# STM32F7.net
KiCad netlist of a schematic drawn in Altium Designer
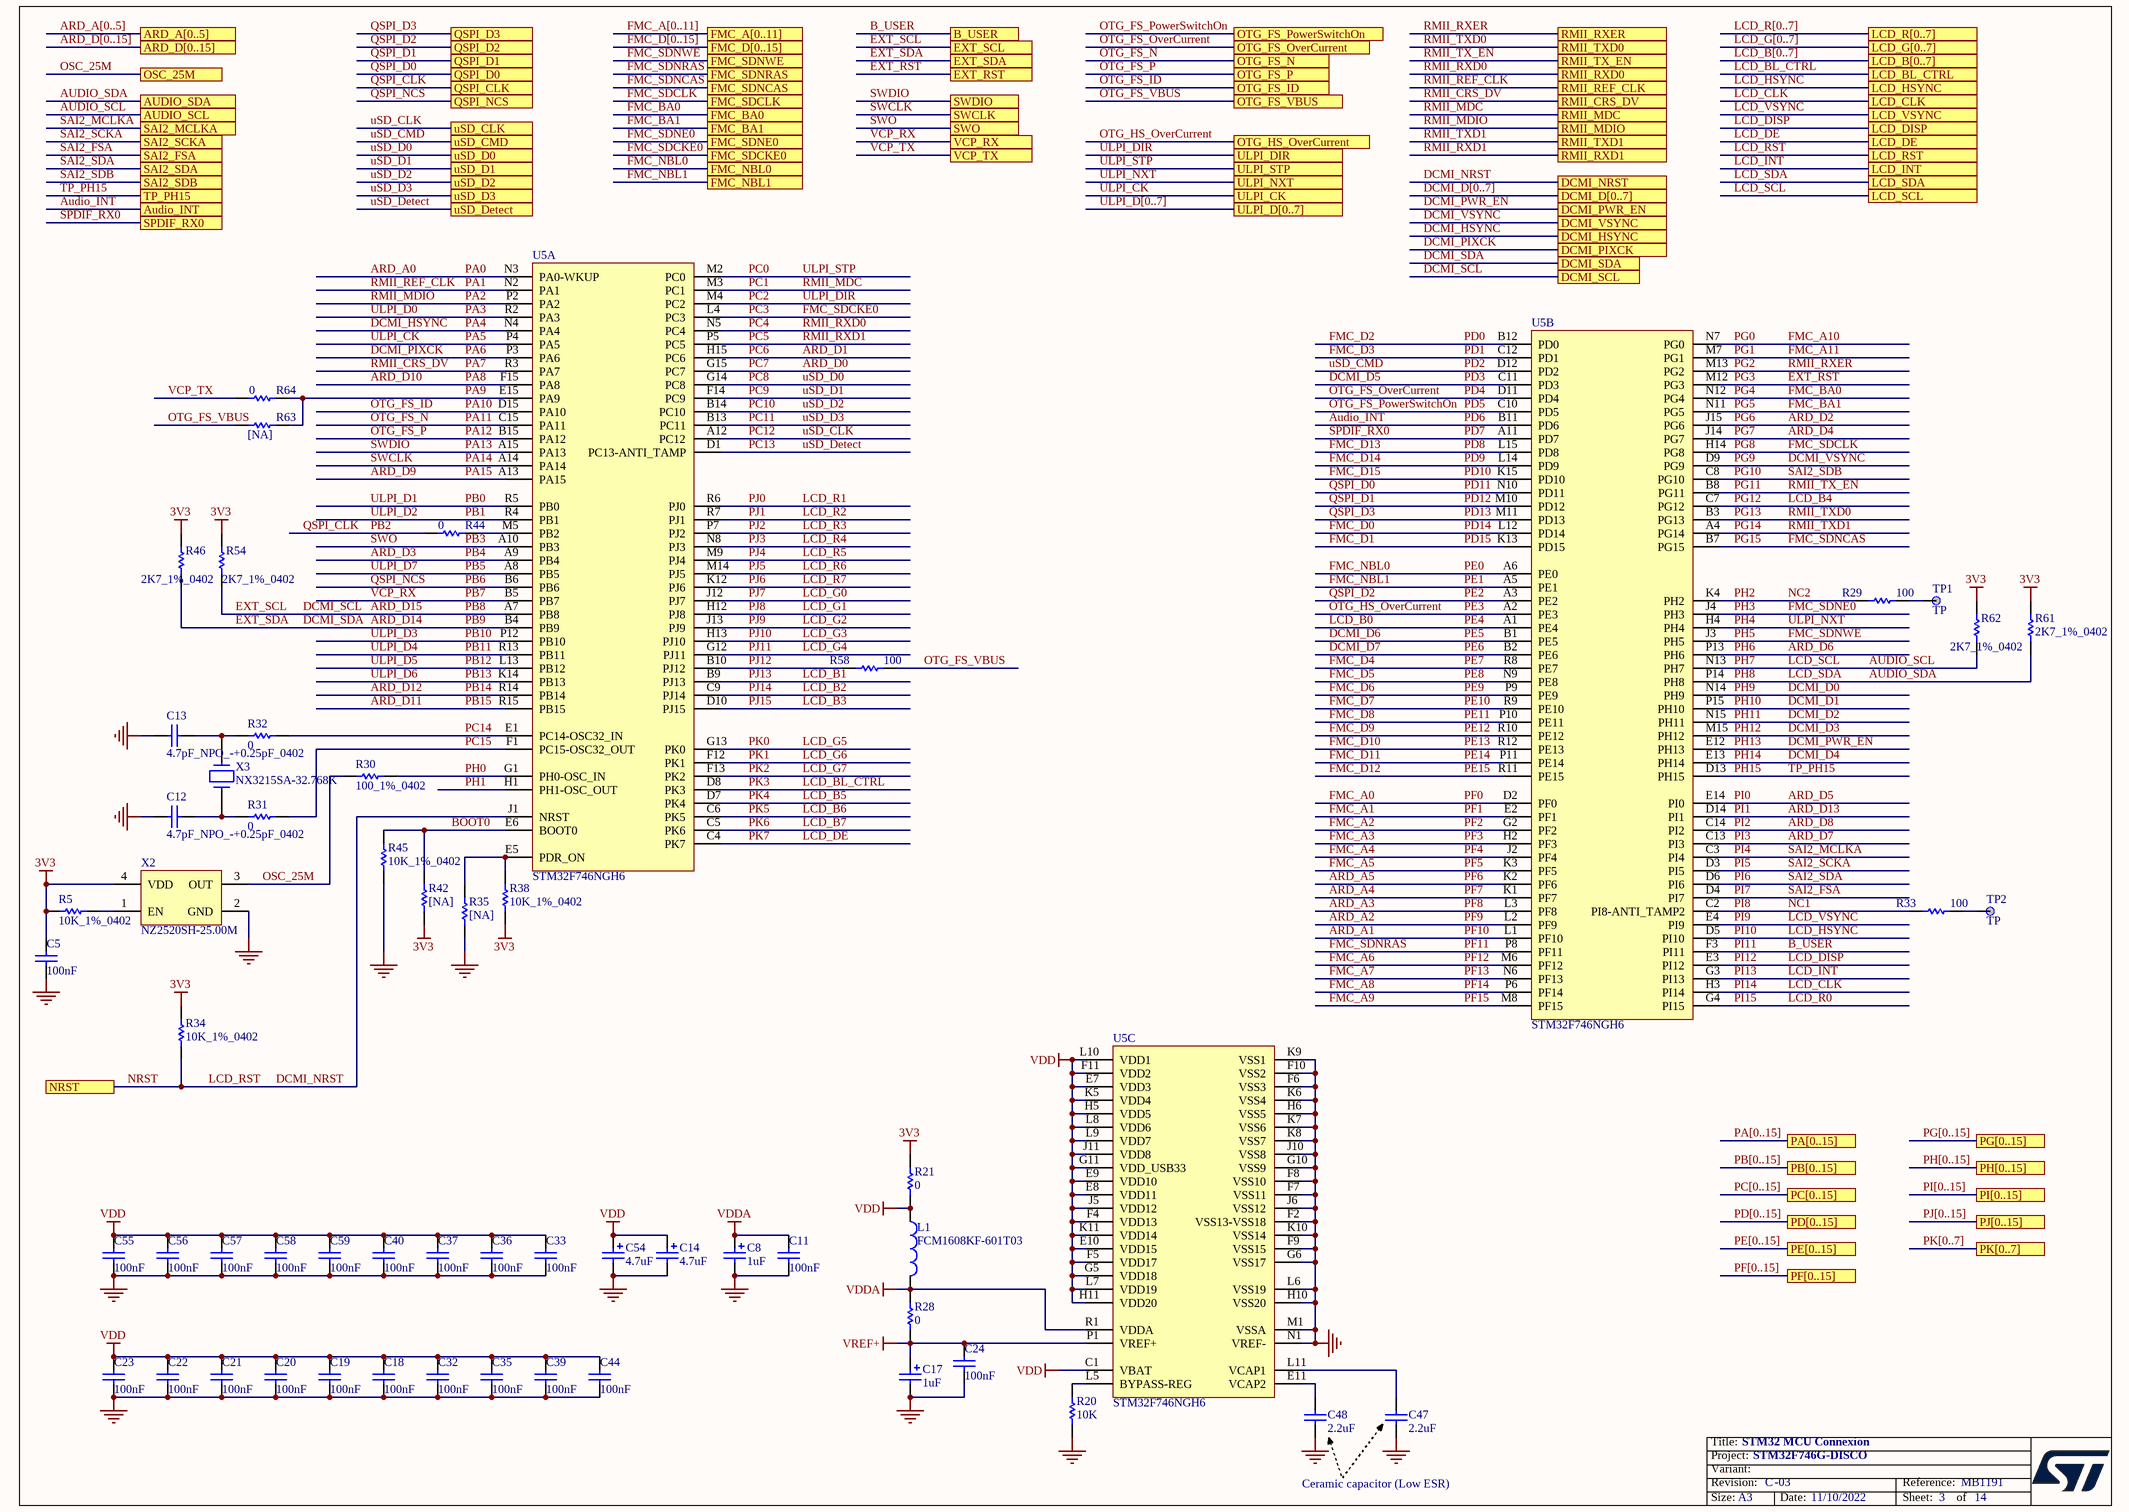
[diagram p0: STM32F7.SchDoc]

(export (version "E")
  (design (tool "Eeschema 10.0.6"))
  (components
    (comp (ref "C5")
      (value "100nF")
      (footprint "0402C")
      (description "Capacitor,100nF,16V,X7R,10%,0402,YAGEO")
      (libsource (lib "MCD_TOOLS") (part "Cap_100nF_X7R_10%_0402"))
    )
    (comp (ref "C8")
      (value "1uF")
      (footprint "TAN-A")
      (description "Polarized Capacitor,1uF,16V,10%,typeA,AVX")
      (libsource (lib "MCD_TOOLS") (part "Cap_1uF_POL_10%_TANA"))
    )
    (comp (ref "C11")
      (value "100nF")
      (footprint "0402C")
      (description "Capacitor,100nF,16V,X7R,10%,0402,YAGEO")
      (libsource (lib "MCD_TOOLS") (part "Cap_100nF_X7R_10%_0402"))
    )
    (comp (ref "C12")
      (value "4.7pF_NPO_-+0.25pF_0402")
      (footprint "0402C")
      (description "Capacitor, 4.7pF, 50V, NPO, -+0.25pF, 0402, YAGEO")
      (libsource (lib "MCD_TOOLS") (part "Cap_4.7pF_NPO_-+0.25pF_0402"))
    )
    (comp (ref "C13")
      (value "4.7pF_NPO_-+0.25pF_0402")
      (footprint "0402C")
      (description "Capacitor, 4.7pF, 50V, NPO, -+0.25pF, 0402, YAGEO")
      (libsource (lib "MCD_TOOLS") (part "Cap_4.7pF_NPO_-+0.25pF_0402"))
    )
    (comp (ref "C14")
      (value "4.7uF")
      (footprint "TAN-A")
      (description "Polarized Capacitor,4.7uF,16V,10%,typeA,AVX")
      (libsource (lib "MCD_TOOLS") (part "Cap_4.7uF_POL_10%_TANA"))
    )
    (comp (ref "C17")
      (value "1uF")
      (footprint "TAN-A")
      (description "Polarized Capacitor,1uF,16V,10%,typeA,AVX")
      (libsource (lib "MCD_TOOLS") (part "Cap_1uF_POL_10%_TANA"))
    )
    (comp (ref "C18")
      (value "100nF")
      (footprint "0402C")
      (description "Capacitor,100nF,16V,X7R,10%,0402,YAGEO")
      (libsource (lib "MCD_TOOLS") (part "Cap_100nF_X7R_10%_0402"))
    )
    (comp (ref "C19")
      (value "100nF")
      (footprint "0402C")
      (description "Capacitor,100nF,16V,X7R,10%,0402,YAGEO")
      (libsource (lib "MCD_TOOLS") (part "Cap_100nF_X7R_10%_0402"))
    )
    (comp (ref "C20")
      (value "100nF")
      (footprint "0402C")
      (description "Capacitor,100nF,16V,X7R,10%,0402,YAGEO")
      (libsource (lib "MCD_TOOLS") (part "Cap_100nF_X7R_10%_0402"))
    )
    (comp (ref "C21")
      (value "100nF")
      (footprint "0402C")
      (description "Capacitor,100nF,16V,X7R,10%,0402,YAGEO")
      (libsource (lib "MCD_TOOLS") (part "Cap_100nF_X7R_10%_0402"))
    )
    (comp (ref "C22")
      (value "100nF")
      (footprint "0402C")
      (description "Capacitor,100nF,16V,X7R,10%,0402,YAGEO")
      (libsource (lib "MCD_TOOLS") (part "Cap_100nF_X7R_10%_0402"))
    )
    (comp (ref "C23")
      (value "100nF")
      (footprint "0402C")
      (description "Capacitor,100nF,16V,X7R,10%,0402,YAGEO")
      (libsource (lib "MCD_TOOLS") (part "Cap_100nF_X7R_10%_0402"))
    )
    (comp (ref "C24")
      (value "100nF")
      (footprint "0402C")
      (description "Capacitor,100nF,16V,X7R,10%,0402,YAGEO")
      (libsource (lib "MCD_TOOLS") (part "Cap_100nF_X7R_10%_0402"))
    )
    (comp (ref "C32")
      (value "100nF")
      (footprint "0402C")
      (description "Capacitor,100nF,16V,X7R,10%,0402,YAGEO")
      (libsource (lib "MCD_TOOLS") (part "Cap_100nF_X7R_10%_0402"))
    )
    (comp (ref "C33")
      (value "100nF")
      (footprint "0402C")
      (description "Capacitor,100nF,16V,X7R,10%,0402,YAGEO")
      (libsource (lib "MCD_TOOLS") (part "Cap_100nF_X7R_10%_0402"))
    )
    (comp (ref "C35")
      (value "100nF")
      (footprint "0402C")
      (description "Capacitor,100nF,16V,X7R,10%,0402,YAGEO")
      (libsource (lib "MCD_TOOLS") (part "Cap_100nF_X7R_10%_0402"))
    )
    (comp (ref "C36")
      (value "100nF")
      (footprint "0402C")
      (description "Capacitor,100nF,16V,X7R,10%,0402,YAGEO")
      (libsource (lib "MCD_TOOLS") (part "Cap_100nF_X7R_10%_0402"))
    )
    (comp (ref "C37")
      (value "100nF")
      (footprint "0402C")
      (description "Capacitor,100nF,16V,X7R,10%,0402,YAGEO")
      (libsource (lib "MCD_TOOLS") (part "Cap_100nF_X7R_10%_0402"))
    )
    (comp (ref "C39")
      (value "100nF")
      (footprint "0402C")
      (description "Capacitor,100nF,16V,X7R,10%,0402,YAGEO")
      (libsource (lib "MCD_TOOLS") (part "Cap_100nF_X7R_10%_0402"))
    )
    (comp (ref "C40")
      (value "100nF")
      (footprint "0402C")
      (description "Capacitor,100nF,16V,X7R,10%,0402,YAGEO")
      (libsource (lib "MCD_TOOLS") (part "Cap_100nF_X7R_10%_0402"))
    )
    (comp (ref "C44")
      (value "100nF")
      (footprint "0402C")
      (description "Capacitor,100nF,16V,X7R,10%,0402,YAGEO")
      (libsource (lib "MCD_TOOLS") (part "Cap_100nF_X7R_10%_0402"))
    )
    (comp (ref "C47")
      (value "2.2uF")
      (footprint "1206C")
      (description "Capacitor,2.2uF,16V, X7R,10%,1206,YAGEO")
      (libsource (lib "MCD_TOOLS") (part "Cap_2.2uF_X7R_10%_1206"))
    )
    (comp (ref "C48")
      (value "2.2uF")
      (footprint "1206C")
      (description "Capacitor,2.2uF,16V, X7R,10%,1206,YAGEO")
      (libsource (lib "MCD_TOOLS") (part "Cap_2.2uF_X7R_10%_1206"))
    )
    (comp (ref "C54")
      (value "4.7uF")
      (footprint "TAN-A")
      (description "Polarized Capacitor,4.7uF,16V,10%,typeA,AVX")
      (libsource (lib "MCD_TOOLS") (part "Cap_4.7uF_POL_10%_TANA"))
    )
    (comp (ref "C55")
      (value "100nF")
      (footprint "0402C")
      (description "Capacitor,100nF,16V,X7R,10%,0402,YAGEO")
      (libsource (lib "MCD_TOOLS") (part "Cap_100nF_X7R_10%_0402"))
    )
    (comp (ref "C56")
      (value "100nF")
      (footprint "0402C")
      (description "Capacitor,100nF,16V,X7R,10%,0402,YAGEO")
      (libsource (lib "MCD_TOOLS") (part "Cap_100nF_X7R_10%_0402"))
    )
    (comp (ref "C57")
      (value "100nF")
      (footprint "0402C")
      (description "Capacitor,100nF,16V,X7R,10%,0402,YAGEO")
      (libsource (lib "MCD_TOOLS") (part "Cap_100nF_X7R_10%_0402"))
    )
    (comp (ref "C58")
      (value "100nF")
      (footprint "0402C")
      (description "Capacitor,100nF,16V,X7R,10%,0402,YAGEO")
      (libsource (lib "MCD_TOOLS") (part "Cap_100nF_X7R_10%_0402"))
    )
    (comp (ref "C59")
      (value "100nF")
      (footprint "0402C")
      (description "Capacitor,100nF,16V,X7R,10%,0402,YAGEO")
      (libsource (lib "MCD_TOOLS") (part "Cap_100nF_X7R_10%_0402"))
    )
    (comp (ref "L1")
      (value "FCM1608KF-601T03")
      (footprint "0603L")
      (description "Bead,600R,350mA,0603,FCM1608KF-601T03,Tai-tech")
      (libsource (lib "MCD_TOOLS") (part "BEAD_600R_350MA_0603"))
    )
    (comp (ref "R5")
      (value "10K_1%_0402")
      (footprint "0402R")
      (description "Resistor,10K,0402,1%,YAGEO")
      (libsource (lib "MCD_TOOLS") (part "Res_10K_1%_0402"))
    )
    (comp (ref "R20")
      (value "10K")
      (footprint "0402R")
      (description "Resistor,10K,0402,1%,YAGEO")
      (libsource (lib "MCD_TOOLS") (part "Res_10K_1%_0402"))
    )
    (comp (ref "R21")
      (value "0")
      (footprint "0603R-GS")
      (description "Resistor,0,0603,5%,YAGEO")
      (libsource (lib "MCD_TOOLS") (part "Res_0_5%_0603"))
    )
    (comp (ref "R28")
      (value "0")
      (footprint "0603R-GS")
      (description "Resistor,0,0603,5%,YAGEO")
      (libsource (lib "MCD_TOOLS") (part "Res_0_5%_0603"))
    )
    (comp (ref "R29")
      (value "100")
      (footprint "0402R")
      (description "Resistor,100,0402,1%,YAGEO")
      (libsource (lib "MCD_TOOLS") (part "Res_100_1%_0402"))
    )
    (comp (ref "R30")
      (value "100_1%_0402")
      (footprint "0402R")
      (description "Resistor,100,0402,1%,YAGEO")
      (libsource (lib "MCD_TOOLS") (part "Res_100_1%_0402"))
    )
    (comp (ref "R31")
      (value "0")
      (footprint "0402R")
      (description "Resistor,0,0402,5%,YAGEO")
      (libsource (lib "MCD_TOOLS") (part "Res_0_5%_0402"))
    )
    (comp (ref "R32")
      (value "0")
      (footprint "0402R")
      (description "Resistor,0,0402,5%,YAGEO")
      (libsource (lib "MCD_TOOLS") (part "Res_0_5%_0402"))
    )
    (comp (ref "R33")
      (value "100")
      (footprint "0402R")
      (description "Resistor,100,0402,1%,YAGEO")
      (libsource (lib "MCD_TOOLS") (part "Res_100_1%_0402"))
    )
    (comp (ref "R34")
      (value "10K_1%_0402")
      (footprint "0402R")
      (description "Resistor,10K,0402,1%,YAGEO")
      (libsource (lib "MCD_TOOLS") (part "Res_10K_1%_0402"))
    )
    (comp (ref "R35")
      (value "[NA]")
      (footprint "0402R")
      (description "Resistor,[NA],0402")
      (libsource (lib "MCD_TOOLS") (part "Res_NA_0402"))
    )
    (comp (ref "R38")
      (value "10K_1%_0402")
      (footprint "0402R")
      (description "Resistor,10K,0402,1%,YAGEO")
      (libsource (lib "MCD_TOOLS") (part "Res_10K_1%_0402"))
    )
    (comp (ref "R42")
      (value "[NA]")
      (footprint "0402R")
      (description "Resistor,[NA],0402")
      (libsource (lib "MCD_TOOLS") (part "Res_NA_0402"))
    )
    (comp (ref "R44")
      (value "0")
      (footprint "0402R")
      (description "Resistor,0,0402,5%,YAGEO")
      (libsource (lib "MCD_TOOLS") (part "Res_0_5%_0402"))
    )
    (comp (ref "R45")
      (value "10K_1%_0402")
      (footprint "0402R")
      (description "Resistor,10K,0402,1%,YAGEO")
      (libsource (lib "MCD_TOOLS") (part "Res_10K_1%_0402"))
    )
    (comp (ref "R46")
      (value "2K7_1%_0402")
      (footprint "0402R")
      (description "Resistor,2K7,0402,1%,YAGEO")
      (libsource (lib "MCD_TOOLS") (part "Res_2K7_1%_0402"))
    )
    (comp (ref "R54")
      (value "2K7_1%_0402")
      (footprint "0402R")
      (description "Resistor,2K7,0402,1%,YAGEO")
      (libsource (lib "MCD_TOOLS") (part "Res_2K7_1%_0402"))
    )
    (comp (ref "R58")
      (value "100")
      (footprint "0402R")
      (description "Resistor,100,0402,1%,YAGEO")
      (libsource (lib "MCD_TOOLS") (part "Res_100_1%_0402"))
    )
    (comp (ref "R61")
      (value "2K7_1%_0402")
      (footprint "0402R")
      (description "Resistor,2K7,0402,1%,YAGEO")
      (libsource (lib "MCD_TOOLS") (part "Res_2K7_1%_0402"))
    )
    (comp (ref "R62")
      (value "2K7_1%_0402")
      (footprint "0402R")
      (description "Resistor,2K7,0402,1%,YAGEO")
      (libsource (lib "MCD_TOOLS") (part "Res_2K7_1%_0402"))
    )
    (comp (ref "R63")
      (value "[NA]")
      (footprint "0402R")
      (description "Resistor,[NA],0402")
      (libsource (lib "MCD_TOOLS") (part "Res_NA_0402"))
    )
    (comp (ref "R64")
      (value "0")
      (footprint "0402R")
      (description "Resistor,0,0402,5%,YAGEO")
      (libsource (lib "MCD_TOOLS") (part "Res_0_5%_0402"))
    )
    (comp (ref "TP1")
      (value "TP")
      (footprint "SMDTEST-1MM")
      (description "Test Point")
      (libsource (lib "MCD_TOOLS") (part "TP"))
    )
    (comp (ref "TP2")
      (value "TP")
      (footprint "SMDTEST-1MM")
      (description "Test Point")
      (libsource (lib "MCD_TOOLS") (part "TP"))
    )
    (comp (ref "U5")
      (value "STM32F746NGH6")
      (footprint "BGA216_0R8_13X13_SKT")
      (description "STM32F746NGH6 (STM32F7 Birdie) TBGA216")
      (libsource (lib "MCD_TOOLS") (part "STM32F746NGH6U"))
    )
    (comp (ref "X2")
      (value "NZ2520SH-25.00M")
      (footprint "NZ2520SH_4P")
      (description "Oscillator 25.00Mhz, -+50PPM, 3.3V, Temp -55 to +125°C")
      (libsource (lib "MCD_TOOLS") (part "OSC_25M_NZ2520SB"))
    )
    (comp (ref "X3")
      (value "NX3215SA-32.768K")
      (footprint "XTAL_2SM_3R2X1R5")
      (description "Crystal 32.768kHz, 6pF, -+20PPM, R=50K, SMD")
      (libsource (lib "MCD_TOOLS") (part "XTAL_32K_NX3215SA"))
    )
  )
  (nets
    (net (code "1") (name "/ARD_A0") (class "Default")
      (node (ref "U5") (pin "N3") (pinfunction "PA0-WKUP_N3") (pintype "passive"))
    )
    (net (code "2") (name "/ARD_A1") (class "Default")
      (node (ref "U5") (pin "L1") (pinfunction "PF10_L1") (pintype "passive"))
    )
    (net (code "3") (name "/ARD_A2") (class "Default")
      (node (ref "U5") (pin "L2") (pinfunction "PF9_L2") (pintype "passive"))
    )
    (net (code "4") (name "/ARD_A3") (class "Default")
      (node (ref "U5") (pin "L3") (pinfunction "PF8_L3") (pintype "passive"))
    )
    (net (code "5") (name "/ARD_A4") (class "Default")
      (node (ref "U5") (pin "K1") (pinfunction "PF7_K1") (pintype "passive"))
    )
    (net (code "6") (name "/ARD_A5") (class "Default")
      (node (ref "U5") (pin "K2") (pinfunction "PF6_K2") (pintype "passive"))
    )
    (net (code "8") (name "/ARD_D0") (class "Default")
      (node (ref "U5") (pin "G15") (pinfunction "PC7_G15") (pintype "passive"))
    )
    (net (code "9") (name "/ARD_D1") (class "Default")
      (node (ref "U5") (pin "H15") (pinfunction "PC6_H15") (pintype "passive"))
    )
    (net (code "10") (name "/ARD_D2") (class "Default")
      (node (ref "U5") (pin "J15") (pinfunction "PG6_J15") (pintype "passive"))
    )
    (net (code "11") (name "/ARD_D3") (class "Default")
      (node (ref "U5") (pin "A9") (pinfunction "PB4_A9") (pintype "passive"))
    )
    (net (code "12") (name "/ARD_D4") (class "Default")
      (node (ref "U5") (pin "J14") (pinfunction "PG7_J14") (pintype "passive"))
    )
    (net (code "13") (name "/ARD_D5") (class "Default")
      (node (ref "U5") (pin "E14") (pinfunction "PI0_E14") (pintype "passive"))
    )
    (net (code "14") (name "/ARD_D6") (class "Default")
      (node (ref "U5") (pin "P13") (pinfunction "PH6_P13") (pintype "passive"))
    )
    (net (code "15") (name "/ARD_D7") (class "Default")
      (node (ref "U5") (pin "C13") (pinfunction "PI3_C13") (pintype "passive"))
    )
    (net (code "16") (name "/ARD_D8") (class "Default")
      (node (ref "U5") (pin "C14") (pinfunction "PI2_C14") (pintype "passive"))
    )
    (net (code "17") (name "/ARD_D9") (class "Default")
      (node (ref "U5") (pin "A13") (pinfunction "PA15_A13") (pintype "passive"))
    )
    (net (code "18") (name "/ARD_D10") (class "Default")
      (node (ref "U5") (pin "F15") (pinfunction "PA8_F15") (pintype "passive"))
    )
    (net (code "19") (name "/ARD_D11") (class "Default")
      (node (ref "U5") (pin "R15") (pinfunction "PB15_R15") (pintype "passive"))
    )
    (net (code "20") (name "/ARD_D12") (class "Default")
      (node (ref "U5") (pin "R14") (pinfunction "PB14_R14") (pintype "passive"))
    )
    (net (code "21") (name "/ARD_D13") (class "Default")
      (node (ref "U5") (pin "D14") (pinfunction "PI1_D14") (pintype "passive"))
    )
    (net (code "22") (name "/ARD_D14") (class "Default")
      (node (ref "R46") (pin "1") (pinfunction "1_1") (pintype "passive"))
      (node (ref "U5") (pin "B4") (pinfunction "PB9_B4") (pintype "passive"))
    )
    (net (code "23") (name "/ARD_D15") (class "Default")
      (node (ref "R54") (pin "1") (pinfunction "1_1") (pintype "passive"))
      (node (ref "U5") (pin "A7") (pinfunction "PB8_A7") (pintype "passive"))
    )
    (net (code "25") (name "/BOOT0") (class "Default")
      (node (ref "R42") (pin "2") (pinfunction "2_2") (pintype "passive"))
      (node (ref "R45") (pin "2") (pinfunction "2_2") (pintype "passive"))
      (node (ref "U5") (pin "E6") (pinfunction "BOOT0_E6") (pintype "passive"))
    )
    (net (code "26") (name "/DCMI_D0") (class "Default")
      (node (ref "U5") (pin "N14") (pinfunction "PH9_N14") (pintype "passive"))
    )
    (net (code "27") (name "/DCMI_D1") (class "Default")
      (node (ref "U5") (pin "P15") (pinfunction "PH10_P15") (pintype "passive"))
    )
    (net (code "28") (name "/DCMI_D2") (class "Default")
      (node (ref "U5") (pin "N15") (pinfunction "PH11_N15") (pintype "passive"))
    )
    (net (code "29") (name "/DCMI_D3") (class "Default")
      (node (ref "U5") (pin "M15") (pinfunction "PH12_M15") (pintype "passive"))
    )
    (net (code "30") (name "/DCMI_D4") (class "Default")
      (node (ref "U5") (pin "E13") (pinfunction "PH14_E13") (pintype "passive"))
    )
    (net (code "31") (name "/DCMI_D5") (class "Default")
      (node (ref "U5") (pin "C11") (pinfunction "PD3_C11") (pintype "passive"))
    )
    (net (code "32") (name "/DCMI_D6") (class "Default")
      (node (ref "U5") (pin "B1") (pinfunction "PE5_B1") (pintype "passive"))
    )
    (net (code "33") (name "/DCMI_D7") (class "Default")
      (node (ref "U5") (pin "B2") (pinfunction "PE6_B2") (pintype "passive"))
    )
    (net (code "35") (name "/DCMI_NRST") (class "Default")
      (node (ref "R34") (pin "1") (pinfunction "1_1") (pintype "passive"))
      (node (ref "U5") (pin "J1") (pinfunction "NRST_J1") (pintype "passive"))
    )
    (net (code "36") (name "/FMC_A0") (class "Default")
      (node (ref "U5") (pin "D2") (pinfunction "PF0_D2") (pintype "passive"))
    )
    (net (code "37") (name "/FMC_A1") (class "Default")
      (node (ref "U5") (pin "E2") (pinfunction "PF1_E2") (pintype "passive"))
    )
    (net (code "38") (name "/FMC_A2") (class "Default")
      (node (ref "U5") (pin "G2") (pinfunction "PF2_G2") (pintype "passive"))
    )
    (net (code "39") (name "/FMC_A3") (class "Default")
      (node (ref "U5") (pin "H2") (pinfunction "PF3_H2") (pintype "passive"))
    )
    (net (code "40") (name "/FMC_A4") (class "Default")
      (node (ref "U5") (pin "J2") (pinfunction "PF4_J2") (pintype "passive"))
    )
    (net (code "41") (name "/FMC_A5") (class "Default")
      (node (ref "U5") (pin "K3") (pinfunction "PF5_K3") (pintype "passive"))
    )
    (net (code "42") (name "/FMC_A6") (class "Default")
      (node (ref "U5") (pin "M6") (pinfunction "PF12_M6") (pintype "passive"))
    )
    (net (code "43") (name "/FMC_A7") (class "Default")
      (node (ref "U5") (pin "N6") (pinfunction "PF13_N6") (pintype "passive"))
    )
    (net (code "44") (name "/FMC_A8") (class "Default")
      (node (ref "U5") (pin "P6") (pinfunction "PF14_P6") (pintype "passive"))
    )
    (net (code "45") (name "/FMC_A9") (class "Default")
      (node (ref "U5") (pin "M8") (pinfunction "PF15_M8") (pintype "passive"))
    )
    (net (code "46") (name "/FMC_A10") (class "Default")
      (node (ref "U5") (pin "N7") (pinfunction "PG0_N7") (pintype "passive"))
    )
    (net (code "47") (name "/FMC_A11") (class "Default")
      (node (ref "U5") (pin "M7") (pinfunction "PG1_M7") (pintype "passive"))
    )
    (net (code "49") (name "/FMC_D0") (class "Default")
      (node (ref "U5") (pin "L12") (pinfunction "PD14_L12") (pintype "passive"))
    )
    (net (code "50") (name "/FMC_D1") (class "Default")
      (node (ref "U5") (pin "K13") (pinfunction "PD15_K13") (pintype "passive"))
    )
    (net (code "51") (name "/FMC_D2") (class "Default")
      (node (ref "U5") (pin "B12") (pinfunction "PD0_B12") (pintype "passive"))
    )
    (net (code "52") (name "/FMC_D3") (class "Default")
      (node (ref "U5") (pin "C12") (pinfunction "PD1_C12") (pintype "passive"))
    )
    (net (code "53") (name "/FMC_D4") (class "Default")
      (node (ref "U5") (pin "R8") (pinfunction "PE7_R8") (pintype "passive"))
    )
    (net (code "54") (name "/FMC_D5") (class "Default")
      (node (ref "U5") (pin "N9") (pinfunction "PE8_N9") (pintype "passive"))
    )
    (net (code "55") (name "/FMC_D6") (class "Default")
      (node (ref "U5") (pin "P9") (pinfunction "PE9_P9") (pintype "passive"))
    )
    (net (code "56") (name "/FMC_D7") (class "Default")
      (node (ref "U5") (pin "R9") (pinfunction "PE10_R9") (pintype "passive"))
    )
    (net (code "57") (name "/FMC_D8") (class "Default")
      (node (ref "U5") (pin "P10") (pinfunction "PE11_P10") (pintype "passive"))
    )
    (net (code "58") (name "/FMC_D9") (class "Default")
      (node (ref "U5") (pin "R10") (pinfunction "PE12_R10") (pintype "passive"))
    )
    (net (code "59") (name "/FMC_D10") (class "Default")
      (node (ref "U5") (pin "R12") (pinfunction "PE13_R12") (pintype "passive"))
    )
    (net (code "60") (name "/FMC_D11") (class "Default")
      (node (ref "U5") (pin "P11") (pinfunction "PE14_P11") (pintype "passive"))
    )
    (net (code "61") (name "/FMC_D12") (class "Default")
      (node (ref "U5") (pin "R11") (pinfunction "PE15_R11") (pintype "passive"))
    )
    (net (code "62") (name "/FMC_D13") (class "Default")
      (node (ref "U5") (pin "L15") (pinfunction "PD8_L15") (pintype "passive"))
    )
    (net (code "63") (name "/FMC_D14") (class "Default")
      (node (ref "U5") (pin "L14") (pinfunction "PD9_L14") (pintype "passive"))
    )
    (net (code "64") (name "/FMC_D15") (class "Default")
      (node (ref "U5") (pin "K15") (pinfunction "PD10_K15") (pintype "passive"))
    )
    (net (code "66") (name "/LCD_B0") (class "Default")
      (node (ref "U5") (pin "A1") (pinfunction "PE4_A1") (pintype "passive"))
    )
    (net (code "67") (name "/LCD_B1") (class "Default")
      (node (ref "U5") (pin "B9") (pinfunction "PJ13_B9") (pintype "passive"))
    )
    (net (code "68") (name "/LCD_B2") (class "Default")
      (node (ref "U5") (pin "C9") (pinfunction "PJ14_C9") (pintype "passive"))
    )
    (net (code "69") (name "/LCD_B3") (class "Default")
      (node (ref "U5") (pin "D10") (pinfunction "PJ15_D10") (pintype "passive"))
    )
    (net (code "70") (name "/LCD_B4") (class "Default")
      (node (ref "U5") (pin "C7") (pinfunction "PG12_C7") (pintype "passive"))
    )
    (net (code "71") (name "/LCD_B5") (class "Default")
      (node (ref "U5") (pin "D7") (pinfunction "PK4_D7") (pintype "passive"))
    )
    (net (code "72") (name "/LCD_B6") (class "Default")
      (node (ref "U5") (pin "C6") (pinfunction "PK5_C6") (pintype "passive"))
    )
    (net (code "73") (name "/LCD_B7") (class "Default")
      (node (ref "U5") (pin "C5") (pinfunction "PK6_C5") (pintype "passive"))
    )
    (net (code "75") (name "/LCD_G0") (class "Default")
      (node (ref "U5") (pin "J12") (pinfunction "PJ7_J12") (pintype "passive"))
    )
    (net (code "76") (name "/LCD_G1") (class "Default")
      (node (ref "U5") (pin "H12") (pinfunction "PJ8_H12") (pintype "passive"))
    )
    (net (code "77") (name "/LCD_G2") (class "Default")
      (node (ref "U5") (pin "J13") (pinfunction "PJ9_J13") (pintype "passive"))
    )
    (net (code "78") (name "/LCD_G3") (class "Default")
      (node (ref "U5") (pin "H13") (pinfunction "PJ10_H13") (pintype "passive"))
    )
    (net (code "79") (name "/LCD_G4") (class "Default")
      (node (ref "U5") (pin "G12") (pinfunction "PJ11_G12") (pintype "passive"))
    )
    (net (code "80") (name "/LCD_G5") (class "Default")
      (node (ref "U5") (pin "G13") (pinfunction "PK0_G13") (pintype "passive"))
    )
    (net (code "81") (name "/LCD_G6") (class "Default")
      (node (ref "U5") (pin "F12") (pinfunction "PK1_F12") (pintype "passive"))
    )
    (net (code "82") (name "/LCD_G7") (class "Default")
      (node (ref "U5") (pin "F13") (pinfunction "PK2_F13") (pintype "passive"))
    )
    (net (code "84") (name "/LCD_R0") (class "Default")
      (node (ref "U5") (pin "G4") (pinfunction "PI15_G4") (pintype "passive"))
    )
    (net (code "85") (name "/LCD_R1") (class "Default")
      (node (ref "U5") (pin "R6") (pinfunction "PJ0_R6") (pintype "passive"))
    )
    (net (code "86") (name "/LCD_R2") (class "Default")
      (node (ref "U5") (pin "R7") (pinfunction "PJ1_R7") (pintype "passive"))
    )
    (net (code "87") (name "/LCD_R3") (class "Default")
      (node (ref "U5") (pin "P7") (pinfunction "PJ2_P7") (pintype "passive"))
    )
    (net (code "88") (name "/LCD_R4") (class "Default")
      (node (ref "U5") (pin "N8") (pinfunction "PJ3_N8") (pintype "passive"))
    )
    (net (code "89") (name "/LCD_R5") (class "Default")
      (node (ref "U5") (pin "M9") (pinfunction "PJ4_M9") (pintype "passive"))
    )
    (net (code "90") (name "/LCD_R6") (class "Default")
      (node (ref "U5") (pin "M14") (pinfunction "PJ5_M14") (pintype "passive"))
    )
    (net (code "91") (name "/LCD_R7") (class "Default")
      (node (ref "U5") (pin "K12") (pinfunction "PJ6_K12") (pintype "passive"))
    )
    (net (code "93") (name "/OSC_25M") (class "Default")
      (node (ref "R30") (pin "1") (pinfunction "1_1") (pintype "passive"))
      (node (ref "X2") (pin "3") (pinfunction "OUT_3") (pintype "passive"))
    )
    (net (code "94") (name "/OTG_FS_VBUS") (class "Default")
      (node (ref "R58") (pin "2") (pinfunction "2_2") (pintype "passive"))
      (node (ref "R63") (pin "1") (pinfunction "1_1") (pintype "passive"))
    )
    (net (code "95") (name "/PA1") (class "Default")
      (node (ref "U5") (pin "N2") (pinfunction "PA1_N2") (pintype "passive"))
    )
    (net (code "96") (name "/PA2") (class "Default")
      (node (ref "U5") (pin "P2") (pinfunction "PA2_P2") (pintype "passive"))
    )
    (net (code "97") (name "/PA4") (class "Default")
      (node (ref "U5") (pin "N4") (pinfunction "PA4_N4") (pintype "passive"))
    )
    (net (code "98") (name "/PA5") (class "Default")
      (node (ref "U5") (pin "P4") (pinfunction "PA5_P4") (pintype "passive"))
    )
    (net (code "99") (name "/PA6") (class "Default")
      (node (ref "U5") (pin "P3") (pinfunction "PA6_P3") (pintype "passive"))
    )
    (net (code "100") (name "/PA7") (class "Default")
      (node (ref "U5") (pin "R3") (pinfunction "PA7_R3") (pintype "passive"))
    )
    (net (code "101") (name "/PA9") (class "Default")
      (node (ref "R63") (pin "2") (pinfunction "2_2") (pintype "passive"))
      (node (ref "R64") (pin "2") (pinfunction "2_2") (pintype "passive"))
      (node (ref "U5") (pin "E15") (pinfunction "PA9_E15") (pintype "passive"))
    )
    (net (code "102") (name "/PA10") (class "Default")
      (node (ref "U5") (pin "D15") (pinfunction "PA10_D15") (pintype "passive"))
    )
    (net (code "103") (name "/PA11") (class "Default")
      (node (ref "U5") (pin "C15") (pinfunction "PA11_C15") (pintype "passive"))
    )
    (net (code "104") (name "/PA12") (class "Default")
      (node (ref "U5") (pin "B15") (pinfunction "PA12_B15") (pintype "passive"))
    )
    (net (code "105") (name "/PA13") (class "Default")
      (node (ref "U5") (pin "A15") (pinfunction "PA13_A15") (pintype "passive"))
    )
    (net (code "106") (name "/PA14") (class "Default")
      (node (ref "U5") (pin "A14") (pinfunction "PA14_A14") (pintype "passive"))
    )
    (net (code "108") (name "/PB2") (class "Default")
      (node (ref "R44") (pin "1") (pinfunction "1_1") (pintype "passive"))
    )
    (net (code "109") (name "/PB3") (class "Default")
      (node (ref "U5") (pin "A10") (pinfunction "PB3_A10") (pintype "passive"))
    )
    (net (code "110") (name "/PB6") (class "Default")
      (node (ref "U5") (pin "B6") (pinfunction "PB6_B6") (pintype "passive"))
    )
    (net (code "111") (name "/PB7") (class "Default")
      (node (ref "U5") (pin "B5") (pinfunction "PB7_B5") (pintype "passive"))
    )
    (net (code "113") (name "/PC0") (class "Default")
      (node (ref "U5") (pin "M2") (pinfunction "PC0_M2") (pintype "passive"))
    )
    (net (code "114") (name "/PC1") (class "Default")
      (node (ref "U5") (pin "M3") (pinfunction "PC1_M3") (pintype "passive"))
    )
    (net (code "115") (name "/PC2") (class "Default")
      (node (ref "U5") (pin "M4") (pinfunction "PC2_M4") (pintype "passive"))
    )
    (net (code "116") (name "/PC3") (class "Default")
      (node (ref "U5") (pin "L4") (pinfunction "PC3_L4") (pintype "passive"))
    )
    (net (code "117") (name "/PC4") (class "Default")
      (node (ref "U5") (pin "N5") (pinfunction "PC4_N5") (pintype "passive"))
    )
    (net (code "118") (name "/PC5") (class "Default")
      (node (ref "U5") (pin "P5") (pinfunction "PC5_P5") (pintype "passive"))
    )
    (net (code "119") (name "/PC8") (class "Default")
      (node (ref "U5") (pin "G14") (pinfunction "PC8_G14") (pintype "passive"))
    )
    (net (code "120") (name "/PC9") (class "Default")
      (node (ref "U5") (pin "F14") (pinfunction "PC9_F14") (pintype "passive"))
    )
    (net (code "121") (name "/PC10") (class "Default")
      (node (ref "U5") (pin "B14") (pinfunction "PC10_B14") (pintype "passive"))
    )
    (net (code "122") (name "/PC11") (class "Default")
      (node (ref "U5") (pin "B13") (pinfunction "PC11_B13") (pintype "passive"))
    )
    (net (code "123") (name "/PC12") (class "Default")
      (node (ref "U5") (pin "A12") (pinfunction "PC12_A12") (pintype "passive"))
    )
    (net (code "124") (name "/PC13") (class "Default")
      (node (ref "U5") (pin "D1") (pinfunction "PC13-ANTI_TAMP_D1") (pintype "passive"))
    )
    (net (code "125") (name "/PC14") (class "Default")
      (node (ref "R32") (pin "2") (pinfunction "2_2") (pintype "passive"))
      (node (ref "U5") (pin "E1") (pinfunction "PC14-OSC32_IN_E1") (pintype "passive"))
    )
    (net (code "126") (name "/PC15") (class "Default")
      (node (ref "R31") (pin "2") (pinfunction "2_2") (pintype "passive"))
      (node (ref "U5") (pin "F1") (pinfunction "PC15-OSC32_OUT_F1") (pintype "passive"))
    )
    (net (code "128") (name "/PD2") (class "Default")
      (node (ref "U5") (pin "D12") (pinfunction "PD2_D12") (pintype "passive"))
    )
    (net (code "129") (name "/PD4") (class "Default")
      (node (ref "U5") (pin "D11") (pinfunction "PD4_D11") (pintype "passive"))
    )
    (net (code "130") (name "/PD5") (class "Default")
      (node (ref "U5") (pin "C10") (pinfunction "PD5_C10") (pintype "passive"))
    )
    (net (code "131") (name "/PD6") (class "Default")
      (node (ref "U5") (pin "B11") (pinfunction "PD6_B11") (pintype "passive"))
    )
    (net (code "132") (name "/PD7") (class "Default")
      (node (ref "U5") (pin "A11") (pinfunction "PD7_A11") (pintype "passive"))
    )
    (net (code "133") (name "/PD11") (class "Default")
      (node (ref "U5") (pin "N10") (pinfunction "PD11_N10") (pintype "passive"))
    )
    (net (code "134") (name "/PD12") (class "Default")
      (node (ref "U5") (pin "M10") (pinfunction "PD12_M10") (pintype "passive"))
    )
    (net (code "135") (name "/PD13") (class "Default")
      (node (ref "U5") (pin "M11") (pinfunction "PD13_M11") (pintype "passive"))
    )
    (net (code "137") (name "/PE0") (class "Default")
      (node (ref "U5") (pin "A6") (pinfunction "PE0_A6") (pintype "passive"))
    )
    (net (code "138") (name "/PE1") (class "Default")
      (node (ref "U5") (pin "A5") (pinfunction "PE1_A5") (pintype "passive"))
    )
    (net (code "139") (name "/PE2") (class "Default")
      (node (ref "U5") (pin "A3") (pinfunction "PE2_A3") (pintype "passive"))
    )
    (net (code "140") (name "/PE3") (class "Default")
      (node (ref "U5") (pin "A2") (pinfunction "PE3_A2") (pintype "passive"))
    )
    (net (code "142") (name "/PF11") (class "Default")
      (node (ref "U5") (pin "P8") (pinfunction "PF11_P8") (pintype "passive"))
    )
    (net (code "144") (name "/PG2") (class "Default")
      (node (ref "U5") (pin "M13") (pinfunction "PG2_M13") (pintype "passive"))
    )
    (net (code "145") (name "/PG3") (class "Default")
      (node (ref "U5") (pin "M12") (pinfunction "PG3_M12") (pintype "passive"))
    )
    (net (code "146") (name "/PG4") (class "Default")
      (node (ref "U5") (pin "N12") (pinfunction "PG4_N12") (pintype "passive"))
    )
    (net (code "147") (name "/PG5") (class "Default")
      (node (ref "U5") (pin "N11") (pinfunction "PG5_N11") (pintype "passive"))
    )
    (net (code "148") (name "/PG8") (class "Default")
      (node (ref "U5") (pin "H14") (pinfunction "PG8_H14") (pintype "passive"))
    )
    (net (code "149") (name "/PG9") (class "Default")
      (node (ref "U5") (pin "D9") (pinfunction "PG9_D9") (pintype "passive"))
    )
    (net (code "150") (name "/PG10") (class "Default")
      (node (ref "U5") (pin "C8") (pinfunction "PG10_C8") (pintype "passive"))
    )
    (net (code "151") (name "/PG11") (class "Default")
      (node (ref "U5") (pin "B8") (pinfunction "PG11_B8") (pintype "passive"))
    )
    (net (code "152") (name "/PG13") (class "Default")
      (node (ref "U5") (pin "B3") (pinfunction "PG13_B3") (pintype "passive"))
    )
    (net (code "153") (name "/PG14") (class "Default")
      (node (ref "U5") (pin "A4") (pinfunction "PG14_A4") (pintype "passive"))
    )
    (net (code "154") (name "/PG15") (class "Default")
      (node (ref "U5") (pin "B7") (pinfunction "PG15_B7") (pintype "passive"))
    )
    (net (code "156") (name "/PH0") (class "Default")
      (node (ref "R30") (pin "2") (pinfunction "2_2") (pintype "passive"))
      (node (ref "U5") (pin "G1") (pinfunction "PH0-OSC_IN_G1") (pintype "passive"))
    )
    (net (code "157") (name "/PH1") (class "Default")
      (node (ref "U5") (pin "H1") (pinfunction "PH1-OSC_OUT_H1") (pintype "passive"))
    )
    (net (code "158") (name "/PH2") (class "Default")
      (node (ref "R29") (pin "1") (pinfunction "1_1") (pintype "passive"))
      (node (ref "U5") (pin "K4") (pinfunction "PH2_K4") (pintype "passive"))
    )
    (net (code "159") (name "/PH3") (class "Default")
      (node (ref "U5") (pin "J4") (pinfunction "PH3_J4") (pintype "passive"))
    )
    (net (code "160") (name "/PH4") (class "Default")
      (node (ref "U5") (pin "H4") (pinfunction "PH4_H4") (pintype "passive"))
    )
    (net (code "161") (name "/PH5") (class "Default")
      (node (ref "U5") (pin "J3") (pinfunction "PH5_J3") (pintype "passive"))
    )
    (net (code "162") (name "/PH7") (class "Default")
      (node (ref "R62") (pin "1") (pinfunction "1_1") (pintype "passive"))
      (node (ref "U5") (pin "N13") (pinfunction "PH7_N13") (pintype "passive"))
    )
    (net (code "163") (name "/PH8") (class "Default")
      (node (ref "R61") (pin "1") (pinfunction "1_1") (pintype "passive"))
      (node (ref "U5") (pin "P14") (pinfunction "PH8_P14") (pintype "passive"))
    )
    (net (code "164") (name "/PH13") (class "Default")
      (node (ref "U5") (pin "E12") (pinfunction "PH13_E12") (pintype "passive"))
    )
    (net (code "165") (name "/PH15") (class "Default")
      (node (ref "U5") (pin "D13") (pinfunction "PH15_D13") (pintype "passive"))
    )
    (net (code "167") (name "/PI4") (class "Default")
      (node (ref "U5") (pin "C3") (pinfunction "PI4_C3") (pintype "passive"))
    )
    (net (code "168") (name "/PI5") (class "Default")
      (node (ref "U5") (pin "D3") (pinfunction "PI5_D3") (pintype "passive"))
    )
    (net (code "169") (name "/PI6") (class "Default")
      (node (ref "U5") (pin "D6") (pinfunction "PI6_D6") (pintype "passive"))
    )
    (net (code "170") (name "/PI7") (class "Default")
      (node (ref "U5") (pin "D4") (pinfunction "PI7_D4") (pintype "passive"))
    )
    (net (code "171") (name "/PI8") (class "Default")
      (node (ref "R33") (pin "1") (pinfunction "1_1") (pintype "passive"))
      (node (ref "U5") (pin "C2") (pinfunction "PI8-ANTI_TAMP2_C2") (pintype "passive"))
    )
    (net (code "172") (name "/PI9") (class "Default")
      (node (ref "U5") (pin "E4") (pinfunction "PI9_E4") (pintype "passive"))
    )
    (net (code "173") (name "/PI10") (class "Default")
      (node (ref "U5") (pin "D5") (pinfunction "PI10_D5") (pintype "passive"))
    )
    (net (code "174") (name "/PI11") (class "Default")
      (node (ref "U5") (pin "F3") (pinfunction "PI11_F3") (pintype "passive"))
    )
    (net (code "175") (name "/PI12") (class "Default")
      (node (ref "U5") (pin "E3") (pinfunction "PI12_E3") (pintype "passive"))
    )
    (net (code "176") (name "/PI13") (class "Default")
      (node (ref "U5") (pin "G3") (pinfunction "PI13_G3") (pintype "passive"))
    )
    (net (code "177") (name "/PI14") (class "Default")
      (node (ref "U5") (pin "H3") (pinfunction "PI14_H3") (pintype "passive"))
    )
    (net (code "179") (name "/PJ12") (class "Default")
      (node (ref "R58") (pin "1") (pinfunction "1_1") (pintype "passive"))
      (node (ref "U5") (pin "B10") (pinfunction "PJ12_B10") (pintype "passive"))
    )
    (net (code "181") (name "/PK3") (class "Default")
      (node (ref "U5") (pin "D8") (pinfunction "PK3_D8") (pintype "passive"))
    )
    (net (code "182") (name "/PK7") (class "Default")
      (node (ref "U5") (pin "C4") (pinfunction "PK7_C4") (pintype "passive"))
    )
    (net (code "184") (name "/ULPI_D0") (class "Default")
      (node (ref "U5") (pin "R2") (pinfunction "PA3_R2") (pintype "passive"))
    )
    (net (code "185") (name "/ULPI_D1") (class "Default")
      (node (ref "U5") (pin "R5") (pinfunction "PB0_R5") (pintype "passive"))
    )
    (net (code "186") (name "/ULPI_D2") (class "Default")
      (node (ref "U5") (pin "R4") (pinfunction "PB1_R4") (pintype "passive"))
    )
    (net (code "187") (name "/ULPI_D3") (class "Default")
      (node (ref "U5") (pin "P12") (pinfunction "PB10_P12") (pintype "passive"))
    )
    (net (code "188") (name "/ULPI_D4") (class "Default")
      (node (ref "U5") (pin "R13") (pinfunction "PB11_R13") (pintype "passive"))
    )
    (net (code "189") (name "/ULPI_D5") (class "Default")
      (node (ref "U5") (pin "L13") (pinfunction "PB12_L13") (pintype "passive"))
    )
    (net (code "190") (name "/ULPI_D6") (class "Default")
      (node (ref "U5") (pin "K14") (pinfunction "PB13_K14") (pintype "passive"))
    )
    (net (code "191") (name "/ULPI_D7") (class "Default")
      (node (ref "U5") (pin "A8") (pinfunction "PB5_A8") (pintype "passive"))
    )
    (net (code "193") (name "/VCP_TX") (class "Default")
      (node (ref "R64") (pin "1") (pinfunction "1_1") (pintype "passive"))
    )
    (net (code "194") (name "3V3") (class "Default")
      (node (ref "C5") (pin "2") (pinfunction "2_2") (pintype "passive"))
      (node (ref "R21") (pin "2") (pinfunction "2_2") (pintype "passive"))
      (node (ref "R34") (pin "2") (pinfunction "2_2") (pintype "passive"))
      (node (ref "R38") (pin "1") (pinfunction "1_1") (pintype "passive"))
      (node (ref "R42") (pin "1") (pinfunction "1_1") (pintype "passive"))
      (node (ref "R46") (pin "2") (pinfunction "2_2") (pintype "passive"))
      (node (ref "R5") (pin "1") (pinfunction "1_1") (pintype "passive"))
      (node (ref "R54") (pin "2") (pinfunction "2_2") (pintype "passive"))
      (node (ref "R61") (pin "2") (pinfunction "2_2") (pintype "passive"))
      (node (ref "R62") (pin "2") (pinfunction "2_2") (pintype "passive"))
      (node (ref "X2") (pin "4") (pinfunction "VDD_4") (pintype "passive"))
    )
    (net (code "195") (name "GND") (class "Default")
      (node (ref "C11") (pin "1") (pinfunction "1_1") (pintype "passive"))
      (node (ref "C12") (pin "1") (pinfunction "1_1") (pintype "passive"))
      (node (ref "C13") (pin "1") (pinfunction "1_1") (pintype "passive"))
      (node (ref "C14") (pin "2") (pinfunction "2_2") (pintype "passive"))
      (node (ref "C17") (pin "2") (pinfunction "2_2") (pintype "passive"))
      (node (ref "C18") (pin "1") (pinfunction "1_1") (pintype "passive"))
      (node (ref "C19") (pin "1") (pinfunction "1_1") (pintype "passive"))
      (node (ref "C20") (pin "1") (pinfunction "1_1") (pintype "passive"))
      (node (ref "C21") (pin "1") (pinfunction "1_1") (pintype "passive"))
      (node (ref "C22") (pin "1") (pinfunction "1_1") (pintype "passive"))
      (node (ref "C23") (pin "1") (pinfunction "1_1") (pintype "passive"))
      (node (ref "C24") (pin "1") (pinfunction "1_1") (pintype "passive"))
      (node (ref "C32") (pin "1") (pinfunction "1_1") (pintype "passive"))
      (node (ref "C33") (pin "1") (pinfunction "1_1") (pintype "passive"))
      (node (ref "C35") (pin "1") (pinfunction "1_1") (pintype "passive"))
      (node (ref "C36") (pin "1") (pinfunction "1_1") (pintype "passive"))
      (node (ref "C37") (pin "1") (pinfunction "1_1") (pintype "passive"))
      (node (ref "C39") (pin "1") (pinfunction "1_1") (pintype "passive"))
      (node (ref "C40") (pin "1") (pinfunction "1_1") (pintype "passive"))
      (node (ref "C44") (pin "1") (pinfunction "1_1") (pintype "passive"))
      (node (ref "C47") (pin "1") (pinfunction "1_1") (pintype "passive"))
      (node (ref "C48") (pin "1") (pinfunction "1_1") (pintype "passive"))
      (node (ref "C5") (pin "1") (pinfunction "1_1") (pintype "passive"))
      (node (ref "C54") (pin "2") (pinfunction "2_2") (pintype "passive"))
      (node (ref "C55") (pin "1") (pinfunction "1_1") (pintype "passive"))
      (node (ref "C56") (pin "1") (pinfunction "1_1") (pintype "passive"))
      (node (ref "C57") (pin "1") (pinfunction "1_1") (pintype "passive"))
      (node (ref "C58") (pin "1") (pinfunction "1_1") (pintype "passive"))
      (node (ref "C59") (pin "1") (pinfunction "1_1") (pintype "passive"))
      (node (ref "C8") (pin "2") (pinfunction "2_2") (pintype "passive"))
      (node (ref "R20") (pin "1") (pinfunction "1_1") (pintype "passive"))
      (node (ref "R35") (pin "1") (pinfunction "1_1") (pintype "passive"))
      (node (ref "R45") (pin "1") (pinfunction "1_1") (pintype "passive"))
      (node (ref "U5") (pin "F10") (pinfunction "VSS2_F10") (pintype "passive"))
      (node (ref "U5") (pin "F2") (pinfunction "VSS13-VSS18_F2") (pintype "passive"))
      (node (ref "U5") (pin "F6") (pinfunction "VSS3_F6") (pintype "passive"))
      (node (ref "U5") (pin "F7") (pinfunction "VSS11_F7") (pintype "passive"))
      (node (ref "U5") (pin "F8") (pinfunction "VSS10_F8") (pintype "passive"))
      (node (ref "U5") (pin "F9") (pinfunction "VSS15_F9") (pintype "passive"))
      (node (ref "U5") (pin "G10") (pinfunction "VSS9_G10") (pintype "passive"))
      (node (ref "U5") (pin "G6") (pinfunction "VSS17_G6") (pintype "passive"))
      (node (ref "U5") (pin "H10") (pinfunction "VSS20_H10") (pintype "passive"))
      (node (ref "U5") (pin "H6") (pinfunction "VSS5_H6") (pintype "passive"))
      (node (ref "U5") (pin "J10") (pinfunction "VSS8_J10") (pintype "passive"))
      (node (ref "U5") (pin "J6") (pinfunction "VSS12_J6") (pintype "passive"))
      (node (ref "U5") (pin "K10") (pinfunction "VSS14_K10") (pintype "passive"))
      (node (ref "U5") (pin "K6") (pinfunction "VSS4_K6") (pintype "passive"))
      (node (ref "U5") (pin "K7") (pinfunction "VSS6_K7") (pintype "passive"))
      (node (ref "U5") (pin "K8") (pinfunction "VSS7_K8") (pintype "passive"))
      (node (ref "U5") (pin "K9") (pinfunction "VSS1_K9") (pintype "passive"))
      (node (ref "U5") (pin "L6") (pinfunction "VSS19_L6") (pintype "passive"))
      (node (ref "U5") (pin "M1") (pinfunction "VSSA_M1") (pintype "passive"))
      (node (ref "U5") (pin "N1") (pinfunction "VREF-_N1") (pintype "passive"))
      (node (ref "X2") (pin "2") (pinfunction "GND_2") (pintype "passive"))
    )
    (net (code "196") (name "Net-(C12-Pad2)") (class "Default")
      (node (ref "C12") (pin "2") (pinfunction "2_2") (pintype "passive"))
      (node (ref "R31") (pin "1") (pinfunction "1_1") (pintype "passive"))
      (node (ref "X3") (pin "2") (pinfunction "2_2") (pintype "passive"))
    )
    (net (code "197") (name "Net-(C13-Pad2)") (class "Default")
      (node (ref "C13") (pin "2") (pinfunction "2_2") (pintype "passive"))
      (node (ref "R32") (pin "1") (pinfunction "1_1") (pintype "passive"))
      (node (ref "X3") (pin "1") (pinfunction "1_1") (pintype "passive"))
    )
    (net (code "198") (name "Net-(R29-Pad2)") (class "Default")
      (node (ref "R29") (pin "2") (pinfunction "2_2") (pintype "passive"))
      (node (ref "TP1") (pin "1") (pinfunction "1_1") (pintype "passive"))
    )
    (net (code "199") (name "Net-(R33-Pad2)") (class "Default")
      (node (ref "R33") (pin "2") (pinfunction "2_2") (pintype "passive"))
      (node (ref "TP2") (pin "1") (pinfunction "1_1") (pintype "passive"))
    )
    (net (code "200") (name "Net-(U5A-PB2)") (class "Default")
      (node (ref "R44") (pin "2") (pinfunction "2_2") (pintype "passive"))
      (node (ref "U5") (pin "M5") (pinfunction "PB2_M5") (pintype "passive"))
    )
    (net (code "201") (name "Net-(U5A-PDR_ON)") (class "Default")
      (node (ref "R35") (pin "2") (pinfunction "2_2") (pintype "passive"))
      (node (ref "R38") (pin "2") (pinfunction "2_2") (pintype "passive"))
      (node (ref "U5") (pin "E5") (pinfunction "PDR_ON_E5") (pintype "passive"))
    )
    (net (code "202") (name "Net-(U5C-BYPASS-REG)") (class "Default")
      (node (ref "R20") (pin "2") (pinfunction "2_2") (pintype "passive"))
      (node (ref "U5") (pin "L5") (pinfunction "BYPASS-REG_L5") (pintype "passive"))
    )
    (net (code "203") (name "Net-(U5C-VCAP1)") (class "Default")
      (node (ref "C47") (pin "2") (pinfunction "2_2") (pintype "passive"))
      (node (ref "U5") (pin "L11") (pinfunction "VCAP1_L11") (pintype "passive"))
    )
    (net (code "204") (name "Net-(U5C-VCAP2)") (class "Default")
      (node (ref "C48") (pin "2") (pinfunction "2_2") (pintype "passive"))
      (node (ref "U5") (pin "E11") (pinfunction "VCAP2_E11") (pintype "passive"))
    )
    (net (code "205") (name "Net-(X2-EN)") (class "Default")
      (node (ref "R5") (pin "2") (pinfunction "2_2") (pintype "passive"))
      (node (ref "X2") (pin "1") (pinfunction "EN_1") (pintype "passive"))
    )
    (net (code "206") (name "VDD") (class "Default")
      (node (ref "C14") (pin "1") (pinfunction "1_1") (pintype "passive"))
      (node (ref "C18") (pin "2") (pinfunction "2_2") (pintype "passive"))
      (node (ref "C19") (pin "2") (pinfunction "2_2") (pintype "passive"))
      (node (ref "C20") (pin "2") (pinfunction "2_2") (pintype "passive"))
      (node (ref "C21") (pin "2") (pinfunction "2_2") (pintype "passive"))
      (node (ref "C22") (pin "2") (pinfunction "2_2") (pintype "passive"))
      (node (ref "C23") (pin "2") (pinfunction "2_2") (pintype "passive"))
      (node (ref "C32") (pin "2") (pinfunction "2_2") (pintype "passive"))
      (node (ref "C33") (pin "2") (pinfunction "2_2") (pintype "passive"))
      (node (ref "C35") (pin "2") (pinfunction "2_2") (pintype "passive"))
      (node (ref "C36") (pin "2") (pinfunction "2_2") (pintype "passive"))
      (node (ref "C37") (pin "2") (pinfunction "2_2") (pintype "passive"))
      (node (ref "C39") (pin "2") (pinfunction "2_2") (pintype "passive"))
      (node (ref "C40") (pin "2") (pinfunction "2_2") (pintype "passive"))
      (node (ref "C44") (pin "2") (pinfunction "2_2") (pintype "passive"))
      (node (ref "C54") (pin "1") (pinfunction "1_1") (pintype "passive"))
      (node (ref "C55") (pin "2") (pinfunction "2_2") (pintype "passive"))
      (node (ref "C56") (pin "2") (pinfunction "2_2") (pintype "passive"))
      (node (ref "C57") (pin "2") (pinfunction "2_2") (pintype "passive"))
      (node (ref "C58") (pin "2") (pinfunction "2_2") (pintype "passive"))
      (node (ref "C59") (pin "2") (pinfunction "2_2") (pintype "passive"))
      (node (ref "L1") (pin "1") (pinfunction "1_1") (pintype "passive"))
      (node (ref "R21") (pin "1") (pinfunction "1_1") (pintype "passive"))
      (node (ref "U5") (pin "C1") (pinfunction "VBAT_C1") (pintype "passive"))
      (node (ref "U5") (pin "E10") (pinfunction "VDD15_E10") (pintype "passive"))
      (node (ref "U5") (pin "E7") (pinfunction "VDD3_E7") (pintype "passive"))
      (node (ref "U5") (pin "E8") (pinfunction "VDD11_E8") (pintype "passive"))
      (node (ref "U5") (pin "E9") (pinfunction "VDD10_E9") (pintype "passive"))
      (node (ref "U5") (pin "F11") (pinfunction "VDD2_F11") (pintype "passive"))
      (node (ref "U5") (pin "F4") (pinfunction "VDD13_F4") (pintype "passive"))
      (node (ref "U5") (pin "F5") (pinfunction "VDD17_F5") (pintype "passive"))
      (node (ref "U5") (pin "G11") (pinfunction "VDD_USB33_G11") (pintype "passive"))
      (node (ref "U5") (pin "G5") (pinfunction "VDD18_G5") (pintype "passive"))
      (node (ref "U5") (pin "H11") (pinfunction "VDD20_H11") (pintype "passive"))
      (node (ref "U5") (pin "H5") (pinfunction "VDD5_H5") (pintype "passive"))
      (node (ref "U5") (pin "J11") (pinfunction "VDD8_J11") (pintype "passive"))
      (node (ref "U5") (pin "J5") (pinfunction "VDD12_J5") (pintype "passive"))
      (node (ref "U5") (pin "K11") (pinfunction "VDD14_K11") (pintype "passive"))
      (node (ref "U5") (pin "K5") (pinfunction "VDD4_K5") (pintype "passive"))
      (node (ref "U5") (pin "L10") (pinfunction "VDD1_L10") (pintype "passive"))
      (node (ref "U5") (pin "L7") (pinfunction "VDD19_L7") (pintype "passive"))
      (node (ref "U5") (pin "L8") (pinfunction "VDD6_L8") (pintype "passive"))
      (node (ref "U5") (pin "L9") (pinfunction "VDD7_L9") (pintype "passive"))
    )
    (net (code "207") (name "VDDA") (class "Default")
      (node (ref "C11") (pin "2") (pinfunction "2_2") (pintype "passive"))
      (node (ref "C8") (pin "1") (pinfunction "1_1") (pintype "passive"))
      (node (ref "L1") (pin "2") (pinfunction "2_2") (pintype "passive"))
      (node (ref "R28") (pin "1") (pinfunction "1_1") (pintype "passive"))
      (node (ref "U5") (pin "R1") (pinfunction "VDDA_R1") (pintype "passive"))
    )
    (net (code "208") (name "VREF+") (class "Default")
      (node (ref "C17") (pin "1") (pinfunction "1_1") (pintype "passive"))
      (node (ref "C24") (pin "2") (pinfunction "2_2") (pintype "passive"))
      (node (ref "R28") (pin "2") (pinfunction "2_2") (pintype "passive"))
      (node (ref "U5") (pin "P1") (pinfunction "VREF+_P1") (pintype "passive"))
    )
  )
)
